# PCB-GPI-JACK.net
KiCad netlist of a schematic drawn in EAGLE
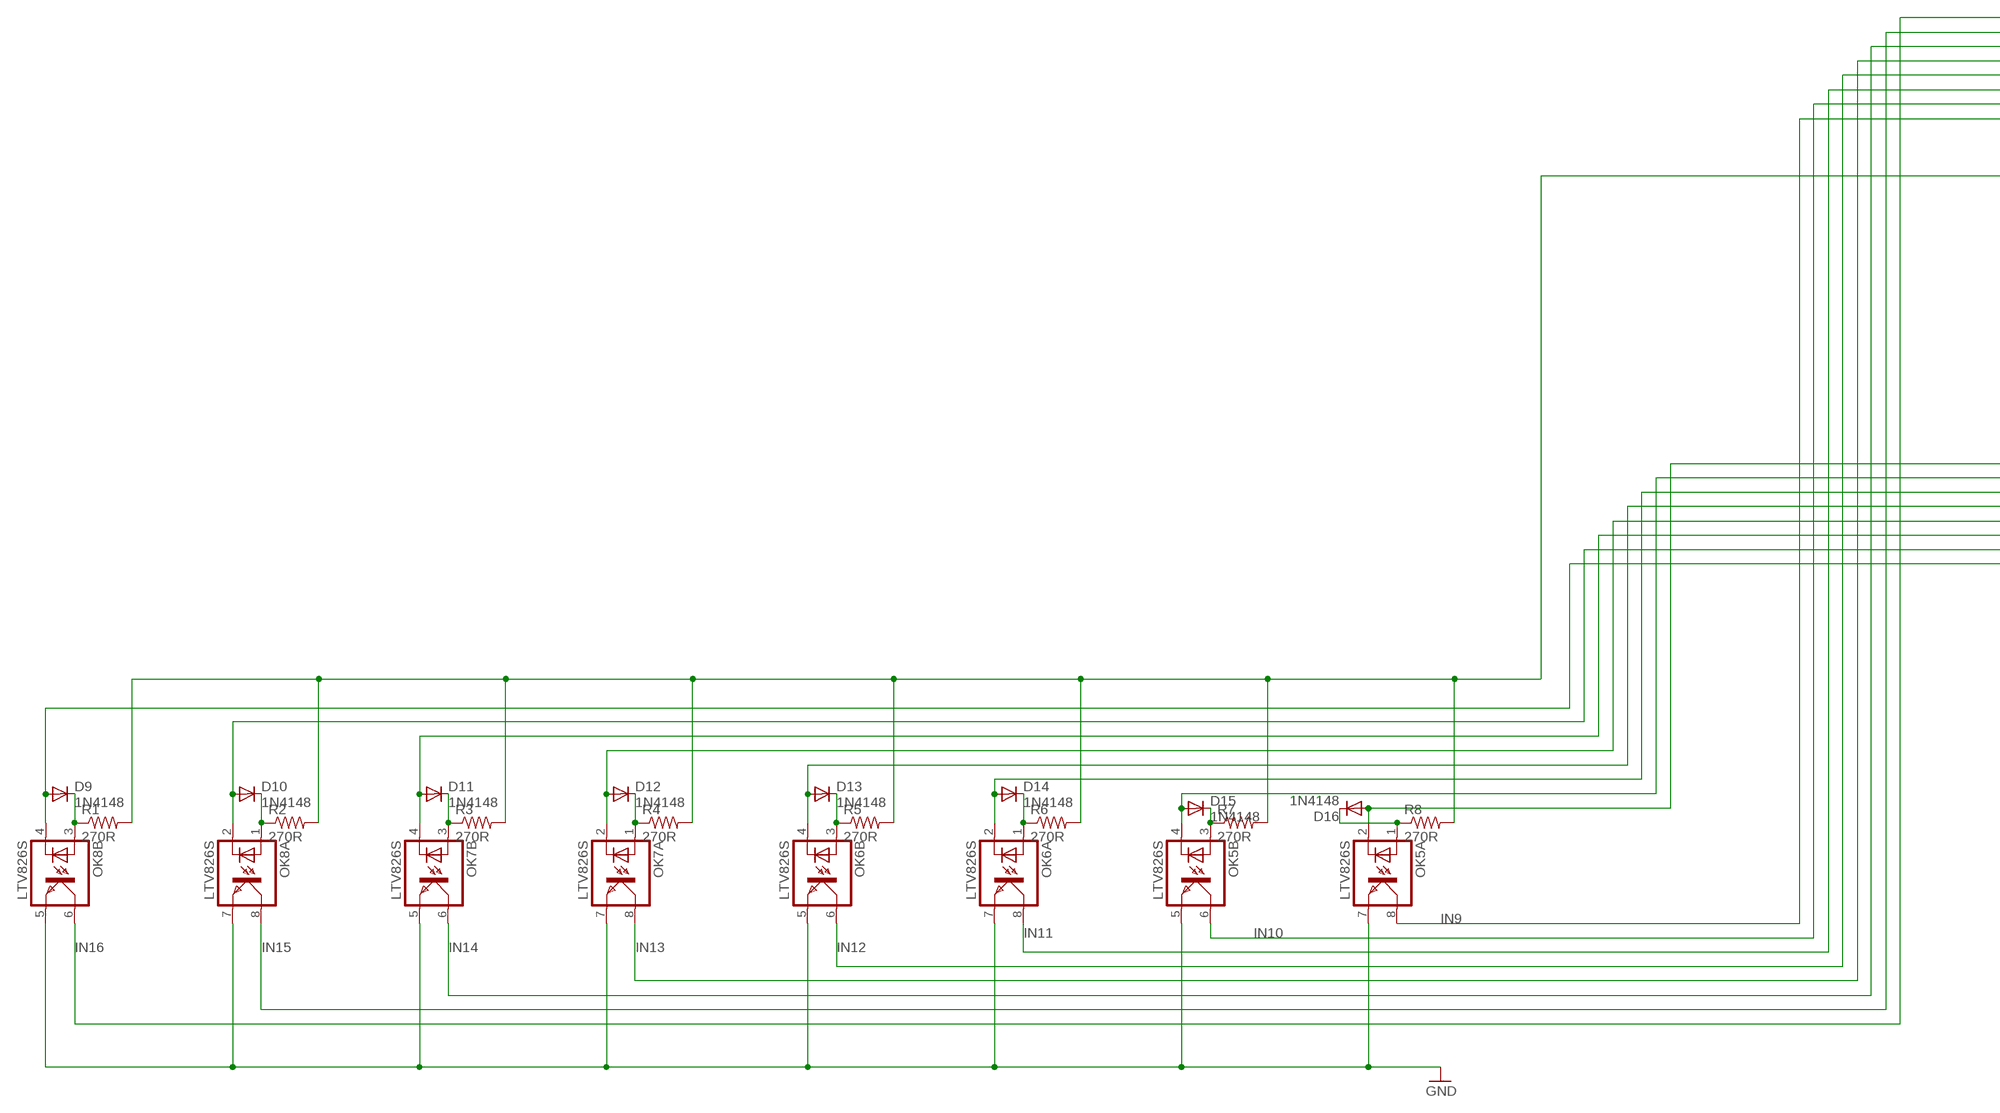
[diagram p0: schematic, sheet 1, part 1 of 2]
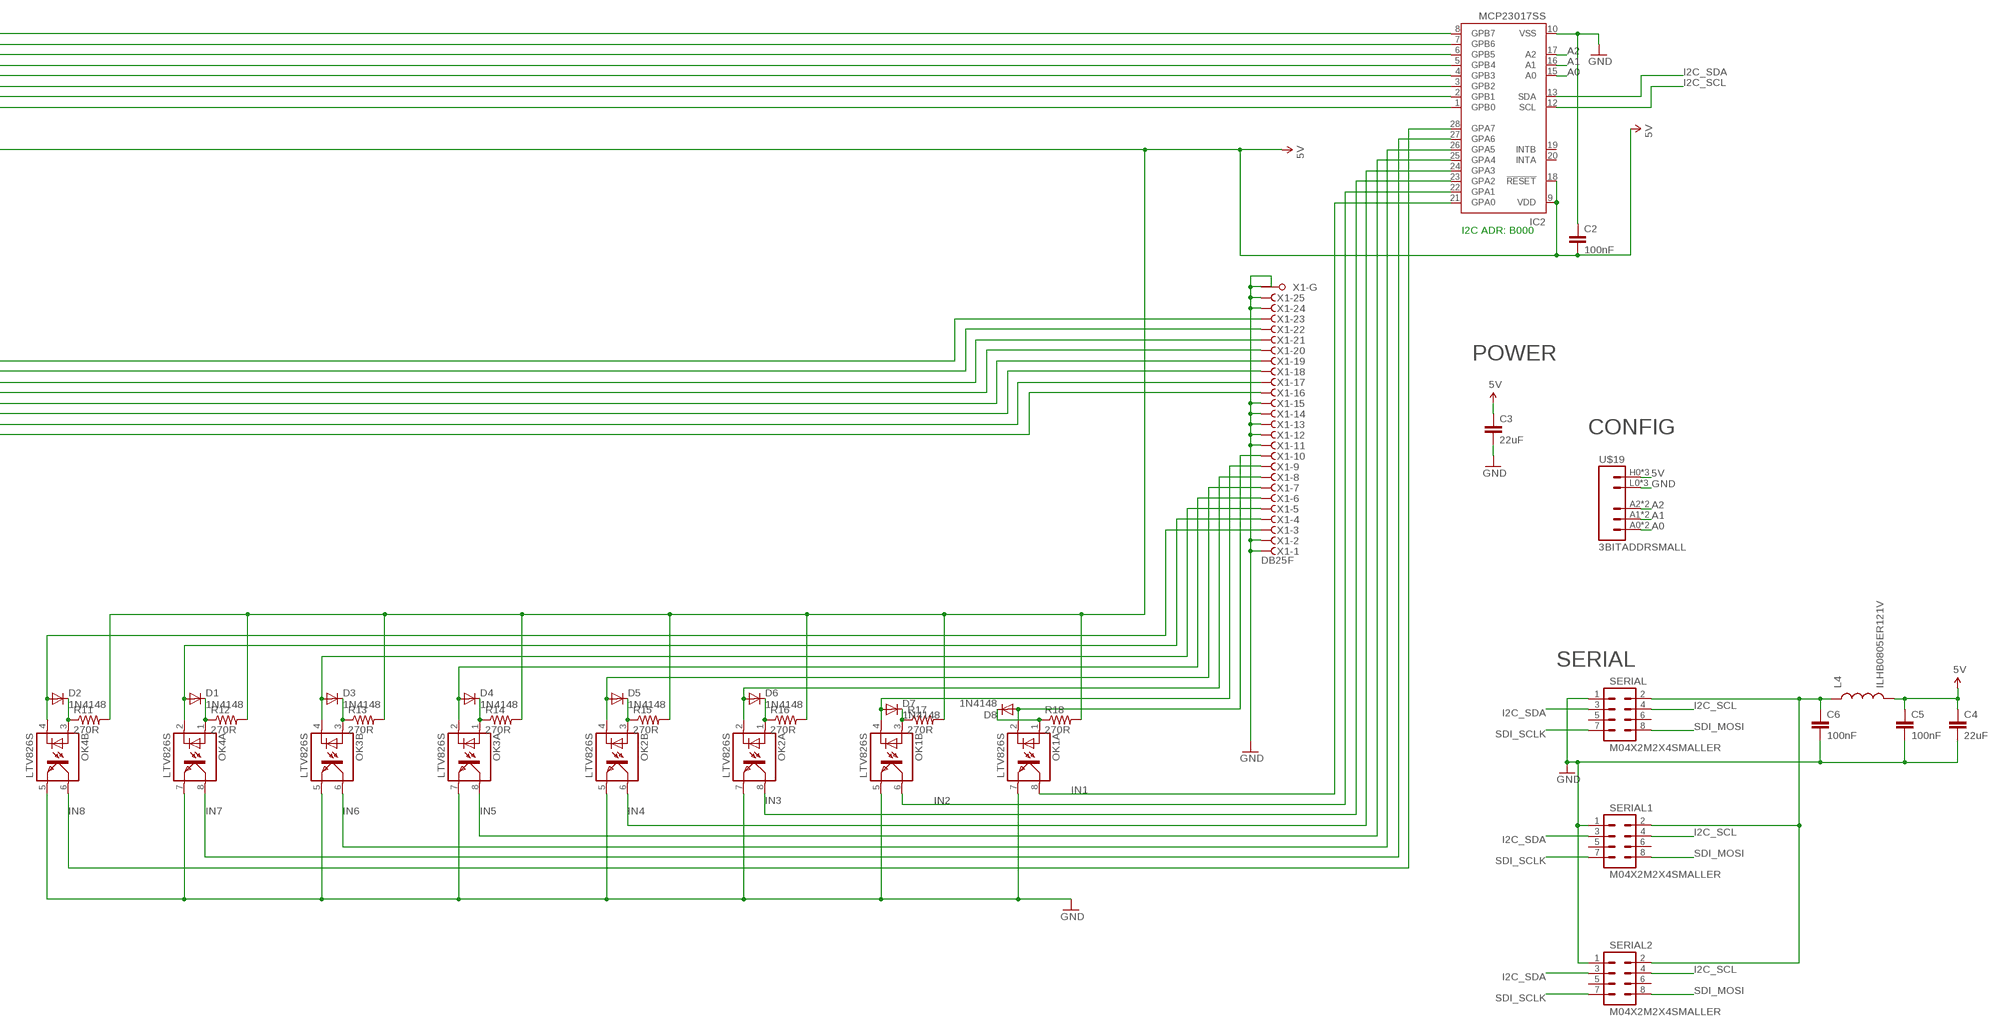
[diagram p1: schematic, sheet 1, part 2 of 2]

(export (version "E")
  (design (tool "Eeschema 10.0.6"))
  (components
    (comp (ref "C2")
      (value "100nF")
      (footprint "eagle-import:0603-CAP")
      (libsource (lib "eagle-import") (part "CAP0603-CAP"))
    )
    (comp (ref "C3")
      (value "22uF")
      (footprint "eagle-import:0805")
      (libsource (lib "eagle-import") (part "CAP0805"))
    )
    (comp (ref "C4")
      (value "22uF")
      (footprint "eagle-import:0805")
      (libsource (lib "eagle-import") (part "CAP0805"))
    )
    (comp (ref "C5")
      (value "100nF")
      (footprint "eagle-import:0603-CAP")
      (libsource (lib "eagle-import") (part "CAP0603-CAP"))
    )
    (comp (ref "C6")
      (value "100nF")
      (footprint "eagle-import:0603-CAP")
      (libsource (lib "eagle-import") (part "CAP0603-CAP"))
    )
    (comp (ref "D1")
      (value "1N4148")
      (footprint "eagle-import:SOD-323")
      (libsource (lib "eagle-import") (part "DIODESOD"))
    )
    (comp (ref "D2")
      (value "1N4148")
      (footprint "eagle-import:SOD-323")
      (libsource (lib "eagle-import") (part "DIODESOD"))
    )
    (comp (ref "D3")
      (value "1N4148")
      (footprint "eagle-import:SOD-323")
      (libsource (lib "eagle-import") (part "DIODESOD"))
    )
    (comp (ref "D4")
      (value "1N4148")
      (footprint "eagle-import:SOD-323")
      (libsource (lib "eagle-import") (part "DIODESOD"))
    )
    (comp (ref "D5")
      (value "1N4148")
      (footprint "eagle-import:SOD-323")
      (libsource (lib "eagle-import") (part "DIODESOD"))
    )
    (comp (ref "D6")
      (value "1N4148")
      (footprint "eagle-import:SOD-323")
      (libsource (lib "eagle-import") (part "DIODESOD"))
    )
    (comp (ref "D7")
      (value "1N4148")
      (footprint "eagle-import:SOD-323")
      (libsource (lib "eagle-import") (part "DIODESOD"))
    )
    (comp (ref "D8")
      (value "1N4148")
      (footprint "eagle-import:SOD-323")
      (libsource (lib "eagle-import") (part "DIODESOD"))
    )
    (comp (ref "D9")
      (value "1N4148")
      (footprint "eagle-import:SOD-323")
      (libsource (lib "eagle-import") (part "DIODESOD"))
    )
    (comp (ref "D10")
      (value "1N4148")
      (footprint "eagle-import:SOD-323")
      (libsource (lib "eagle-import") (part "DIODESOD"))
    )
    (comp (ref "D11")
      (value "1N4148")
      (footprint "eagle-import:SOD-323")
      (libsource (lib "eagle-import") (part "DIODESOD"))
    )
    (comp (ref "D12")
      (value "1N4148")
      (footprint "eagle-import:SOD-323")
      (libsource (lib "eagle-import") (part "DIODESOD"))
    )
    (comp (ref "D13")
      (value "1N4148")
      (footprint "eagle-import:SOD-323")
      (libsource (lib "eagle-import") (part "DIODESOD"))
    )
    (comp (ref "D14")
      (value "1N4148")
      (footprint "eagle-import:SOD-323")
      (libsource (lib "eagle-import") (part "DIODESOD"))
    )
    (comp (ref "D15")
      (value "1N4148")
      (footprint "eagle-import:SOD-323")
      (libsource (lib "eagle-import") (part "DIODESOD"))
    )
    (comp (ref "D16")
      (value "1N4148")
      (footprint "eagle-import:SOD-323")
      (libsource (lib "eagle-import") (part "DIODESOD"))
    )
    (comp (ref "IC2")
      (value "MCP23017SS")
      (footprint "eagle-import:SSOP28")
      (fields (field (name "MF") "MICROCHIP") (field (name "MPN") "MCP23017-E/SS"))
      (libsource (lib "eagle-import") (part "MCP23017SS"))
    )
    (comp (ref "L4")
      (value "ILHB0805ER121V")
      (footprint "eagle-import:0805")
      (libsource (lib "eagle-import") (part "INDUCTOR0805"))
    )
    (comp (ref "OK1")
      (value "LTV826S")
      (footprint "eagle-import:DIL8-SMD")
      (libsource (lib "eagle-import") (part "LTV826S"))
    )
    (comp (ref "OK2")
      (value "LTV826S")
      (footprint "eagle-import:DIL8-SMD")
      (libsource (lib "eagle-import") (part "LTV826S"))
    )
    (comp (ref "OK3")
      (value "LTV826S")
      (footprint "eagle-import:DIL8-SMD")
      (libsource (lib "eagle-import") (part "LTV826S"))
    )
    (comp (ref "OK4")
      (value "LTV826S")
      (footprint "eagle-import:DIL8-SMD")
      (libsource (lib "eagle-import") (part "LTV826S"))
    )
    (comp (ref "OK5")
      (value "LTV826S")
      (footprint "eagle-import:DIL8-SMD")
      (libsource (lib "eagle-import") (part "LTV826S"))
    )
    (comp (ref "OK6")
      (value "LTV826S")
      (footprint "eagle-import:DIL8-SMD")
      (libsource (lib "eagle-import") (part "LTV826S"))
    )
    (comp (ref "OK7")
      (value "LTV826S")
      (footprint "eagle-import:DIL8-SMD")
      (libsource (lib "eagle-import") (part "LTV826S"))
    )
    (comp (ref "OK8")
      (value "LTV826S")
      (footprint "eagle-import:DIL8-SMD")
      (libsource (lib "eagle-import") (part "LTV826S"))
    )
    (comp (ref "R1")
      (value "270R")
      (footprint "eagle-import:0603-RES")
      (libsource (lib "eagle-import") (part "RESISTOR0603-RES"))
    )
    (comp (ref "R2")
      (value "270R")
      (footprint "eagle-import:0603-RES")
      (libsource (lib "eagle-import") (part "RESISTOR0603-RES"))
    )
    (comp (ref "R3")
      (value "270R")
      (footprint "eagle-import:0603-RES")
      (libsource (lib "eagle-import") (part "RESISTOR0603-RES"))
    )
    (comp (ref "R4")
      (value "270R")
      (footprint "eagle-import:0603-RES")
      (libsource (lib "eagle-import") (part "RESISTOR0603-RES"))
    )
    (comp (ref "R5")
      (value "270R")
      (footprint "eagle-import:0603-RES")
      (libsource (lib "eagle-import") (part "RESISTOR0603-RES"))
    )
    (comp (ref "R6")
      (value "270R")
      (footprint "eagle-import:0603-RES")
      (libsource (lib "eagle-import") (part "RESISTOR0603-RES"))
    )
    (comp (ref "R7")
      (value "270R")
      (footprint "eagle-import:0603-RES")
      (libsource (lib "eagle-import") (part "RESISTOR0603-RES"))
    )
    (comp (ref "R8")
      (value "270R")
      (footprint "eagle-import:0603-RES")
      (libsource (lib "eagle-import") (part "RESISTOR0603-RES"))
    )
    (comp (ref "R11")
      (value "270R")
      (footprint "eagle-import:0603-RES")
      (libsource (lib "eagle-import") (part "RESISTOR0603-RES"))
    )
    (comp (ref "R12")
      (value "270R")
      (footprint "eagle-import:0603-RES")
      (libsource (lib "eagle-import") (part "RESISTOR0603-RES"))
    )
    (comp (ref "R13")
      (value "270R")
      (footprint "eagle-import:0603-RES")
      (libsource (lib "eagle-import") (part "RESISTOR0603-RES"))
    )
    (comp (ref "R14")
      (value "270R")
      (footprint "eagle-import:0603-RES")
      (libsource (lib "eagle-import") (part "RESISTOR0603-RES"))
    )
    (comp (ref "R15")
      (value "270R")
      (footprint "eagle-import:0603-RES")
      (libsource (lib "eagle-import") (part "RESISTOR0603-RES"))
    )
    (comp (ref "R16")
      (value "270R")
      (footprint "eagle-import:0603-RES")
      (libsource (lib "eagle-import") (part "RESISTOR0603-RES"))
    )
    (comp (ref "R17")
      (value "270R")
      (footprint "eagle-import:0603-RES")
      (libsource (lib "eagle-import") (part "RESISTOR0603-RES"))
    )
    (comp (ref "R18")
      (value "270R")
      (footprint "eagle-import:0603-RES")
      (libsource (lib "eagle-import") (part "RESISTOR0603-RES"))
    )
    (comp (ref "SERIAL")
      (value "M04X2M2X4SMALLER")
      (footprint "eagle-import:M2X4SMALLER")
      (libsource (lib "eagle-import") (part "M04X2M2X4SMALLER"))
    )
    (comp (ref "SERIAL1")
      (value "M04X2M2X4SMALLER")
      (footprint "eagle-import:M2X4SMALLER")
      (libsource (lib "eagle-import") (part "M04X2M2X4SMALLER"))
    )
    (comp (ref "SERIAL2")
      (value "M04X2M2X4SMALLER")
      (footprint "eagle-import:M2X4SMALLER")
      (libsource (lib "eagle-import") (part "M04X2M2X4SMALLER"))
    )
    (comp (ref "U$19")
      (value "3BITADDRSMALL")
      (footprint "eagle-import:3BITADDR_SMALL")
      (libsource (lib "eagle-import") (part "3BITADDRSMALL"))
    )
    (comp (ref "X1")
      (value "DB25F")
      (footprint "eagle-import:F25HP")
      (libsource (lib "eagle-import") (part "F25HPS"))
    )
  )
  (nets
    (net (code "1") (name "5V") (class "Default")
      (node (ref "C2") (pin "2") (pinfunction "2_2") (pintype "passive"))
      (node (ref "C3") (pin "1") (pinfunction "1_1") (pintype "passive"))
      (node (ref "C4") (pin "1") (pinfunction "1_1") (pintype "passive"))
      (node (ref "C5") (pin "1") (pinfunction "1_1") (pintype "passive"))
      (node (ref "IC2") (pin "18") (pinfunction "~{RESET}_18") (pintype "input"))
      (node (ref "IC2") (pin "9") (pinfunction "VDD_9") (pintype "power_in"))
      (node (ref "L4") (pin "2") (pinfunction "2_2") (pintype "passive"))
      (node (ref "R1") (pin "2") (pinfunction "2_2") (pintype "passive"))
      (node (ref "R11") (pin "2") (pinfunction "2_2") (pintype "passive"))
      (node (ref "R12") (pin "2") (pinfunction "2_2") (pintype "passive"))
      (node (ref "R13") (pin "2") (pinfunction "2_2") (pintype "passive"))
      (node (ref "R14") (pin "2") (pinfunction "2_2") (pintype "passive"))
      (node (ref "R15") (pin "2") (pinfunction "2_2") (pintype "passive"))
      (node (ref "R16") (pin "2") (pinfunction "2_2") (pintype "passive"))
      (node (ref "R17") (pin "2") (pinfunction "2_2") (pintype "passive"))
      (node (ref "R18") (pin "2") (pinfunction "2_2") (pintype "passive"))
      (node (ref "R2") (pin "2") (pinfunction "2_2") (pintype "passive"))
      (node (ref "R3") (pin "2") (pinfunction "2_2") (pintype "passive"))
      (node (ref "R4") (pin "2") (pinfunction "2_2") (pintype "passive"))
      (node (ref "R5") (pin "2") (pinfunction "2_2") (pintype "passive"))
      (node (ref "R6") (pin "2") (pinfunction "2_2") (pintype "passive"))
      (node (ref "R7") (pin "2") (pinfunction "2_2") (pintype "passive"))
      (node (ref "R8") (pin "2") (pinfunction "2_2") (pintype "passive"))
      (node (ref "U$19") (pin "H0") (pinfunction "VCC_H0") (pintype "passive"))
      (node (ref "U$19") (pin "H1") (pinfunction "VCC_H1") (pintype "passive"))
      (node (ref "U$19") (pin "H2") (pinfunction "VCC_H2") (pintype "passive"))
    )
    (net (code "2") (name "A0") (class "Default")
      (node (ref "IC2") (pin "15") (pinfunction "A0_15") (pintype "input"))
      (node (ref "U$19") (pin "A0") (pinfunction "A0_A0") (pintype "passive"))
      (node (ref "U$19") (pin "AS0") (pinfunction "A0_AS0") (pintype "passive"))
    )
    (net (code "3") (name "A1") (class "Default")
      (node (ref "IC2") (pin "16") (pinfunction "A1_16") (pintype "input"))
      (node (ref "U$19") (pin "A1") (pinfunction "A1_A1") (pintype "passive"))
      (node (ref "U$19") (pin "AS1") (pinfunction "A1_AS1") (pintype "passive"))
    )
    (net (code "4") (name "A2") (class "Default")
      (node (ref "IC2") (pin "17") (pinfunction "A2_17") (pintype "input"))
      (node (ref "U$19") (pin "A2") (pinfunction "A2_A2") (pintype "passive"))
      (node (ref "U$19") (pin "AS2") (pinfunction "A2_AS2") (pintype "passive"))
    )
    (net (code "5") (name "GND") (class "Default")
      (node (ref "C2") (pin "1") (pinfunction "1_1") (pintype "passive"))
      (node (ref "C3") (pin "2") (pinfunction "2_2") (pintype "passive"))
      (node (ref "C4") (pin "2") (pinfunction "2_2") (pintype "passive"))
      (node (ref "C5") (pin "2") (pinfunction "2_2") (pintype "passive"))
      (node (ref "C6") (pin "2") (pinfunction "2_2") (pintype "passive"))
      (node (ref "IC2") (pin "10") (pinfunction "VSS_10") (pintype "power_in"))
      (node (ref "OK1") (pin "5") (pinfunction "EMIT_5") (pintype "passive"))
      (node (ref "OK1") (pin "7") (pinfunction "EMIT_7") (pintype "passive"))
      (node (ref "OK2") (pin "5") (pinfunction "EMIT_5") (pintype "passive"))
      (node (ref "OK2") (pin "7") (pinfunction "EMIT_7") (pintype "passive"))
      (node (ref "OK3") (pin "5") (pinfunction "EMIT_5") (pintype "passive"))
      (node (ref "OK3") (pin "7") (pinfunction "EMIT_7") (pintype "passive"))
      (node (ref "OK4") (pin "5") (pinfunction "EMIT_5") (pintype "passive"))
      (node (ref "OK4") (pin "7") (pinfunction "EMIT_7") (pintype "passive"))
      (node (ref "OK5") (pin "5") (pinfunction "EMIT_5") (pintype "passive"))
      (node (ref "OK5") (pin "7") (pinfunction "EMIT_7") (pintype "passive"))
      (node (ref "OK6") (pin "5") (pinfunction "EMIT_5") (pintype "passive"))
      (node (ref "OK6") (pin "7") (pinfunction "EMIT_7") (pintype "passive"))
      (node (ref "OK7") (pin "5") (pinfunction "EMIT_5") (pintype "passive"))
      (node (ref "OK7") (pin "7") (pinfunction "EMIT_7") (pintype "passive"))
      (node (ref "OK8") (pin "5") (pinfunction "EMIT_5") (pintype "passive"))
      (node (ref "OK8") (pin "7") (pinfunction "EMIT_7") (pintype "passive"))
      (node (ref "SERIAL") (pin "1") (pinfunction "1_1") (pintype "passive"))
      (node (ref "SERIAL1") (pin "1") (pinfunction "1_1") (pintype "passive"))
      (node (ref "SERIAL2") (pin "1") (pinfunction "1_1") (pintype "passive"))
      (node (ref "U$19") (pin "L0") (pinfunction "GND_L0") (pintype "passive"))
      (node (ref "U$19") (pin "L1") (pinfunction "GND_L1") (pintype "passive"))
      (node (ref "U$19") (pin "L2") (pinfunction "GND_L2") (pintype "passive"))
      (node (ref "X1") (pin "1") (pinfunction "F_1") (pintype "passive"))
      (node (ref "X1") (pin "11") (pinfunction "F_11") (pintype "passive"))
      (node (ref "X1") (pin "12") (pinfunction "F_12") (pintype "passive"))
      (node (ref "X1") (pin "13") (pinfunction "F_13") (pintype "passive"))
      (node (ref "X1") (pin "14") (pinfunction "F_14") (pintype "passive"))
      (node (ref "X1") (pin "15") (pinfunction "F_15") (pintype "passive"))
      (node (ref "X1") (pin "2") (pinfunction "F_2") (pintype "passive"))
      (node (ref "X1") (pin "24") (pinfunction "F_24") (pintype "passive"))
      (node (ref "X1") (pin "25") (pinfunction "F_25") (pintype "passive"))
      (node (ref "X1") (pin "G1") (pinfunction "G1_G1") (pintype "passive"))
      (node (ref "X1") (pin "G2") (pinfunction "G2_G2") (pintype "passive"))
    )
    (net (code "6") (name "I2C_SCL") (class "Default")
      (node (ref "IC2") (pin "12") (pinfunction "SCL_12") (pintype "input"))
      (node (ref "SERIAL") (pin "4") (pinfunction "4_4") (pintype "passive"))
      (node (ref "SERIAL1") (pin "4") (pinfunction "4_4") (pintype "passive"))
      (node (ref "SERIAL2") (pin "4") (pinfunction "4_4") (pintype "passive"))
    )
    (net (code "7") (name "I2C_SDA") (class "Default")
      (node (ref "IC2") (pin "13") (pinfunction "SDA_13") (pintype "bidirectional"))
      (node (ref "SERIAL") (pin "3") (pinfunction "3_3") (pintype "passive"))
      (node (ref "SERIAL1") (pin "3") (pinfunction "3_3") (pintype "passive"))
      (node (ref "SERIAL2") (pin "3") (pinfunction "3_3") (pintype "passive"))
    )
    (net (code "8") (name "IN1") (class "Default")
      (node (ref "IC2") (pin "21") (pinfunction "GPA0_21") (pintype "bidirectional"))
      (node (ref "OK1") (pin "8") (pinfunction "COL_8") (pintype "passive"))
    )
    (net (code "9") (name "IN2") (class "Default")
      (node (ref "IC2") (pin "22") (pinfunction "GPA1_22") (pintype "bidirectional"))
      (node (ref "OK1") (pin "6") (pinfunction "COL_6") (pintype "passive"))
    )
    (net (code "10") (name "IN3") (class "Default")
      (node (ref "IC2") (pin "23") (pinfunction "GPA2_23") (pintype "bidirectional"))
      (node (ref "OK2") (pin "8") (pinfunction "COL_8") (pintype "passive"))
    )
    (net (code "11") (name "IN4") (class "Default")
      (node (ref "IC2") (pin "24") (pinfunction "GPA3_24") (pintype "bidirectional"))
      (node (ref "OK2") (pin "6") (pinfunction "COL_6") (pintype "passive"))
    )
    (net (code "12") (name "IN5") (class "Default")
      (node (ref "IC2") (pin "25") (pinfunction "GPA4_25") (pintype "bidirectional"))
      (node (ref "OK3") (pin "8") (pinfunction "COL_8") (pintype "passive"))
    )
    (net (code "13") (name "IN6") (class "Default")
      (node (ref "IC2") (pin "26") (pinfunction "GPA5_26") (pintype "bidirectional"))
      (node (ref "OK3") (pin "6") (pinfunction "COL_6") (pintype "passive"))
    )
    (net (code "14") (name "IN7") (class "Default")
      (node (ref "IC2") (pin "27") (pinfunction "GPA6_27") (pintype "bidirectional"))
      (node (ref "OK4") (pin "8") (pinfunction "COL_8") (pintype "passive"))
    )
    (net (code "15") (name "IN8") (class "Default")
      (node (ref "IC2") (pin "28") (pinfunction "GPA7_28") (pintype "bidirectional"))
      (node (ref "OK4") (pin "6") (pinfunction "COL_6") (pintype "passive"))
    )
    (net (code "16") (name "IN9") (class "Default")
      (node (ref "IC2") (pin "1") (pinfunction "GPB0_1") (pintype "bidirectional"))
      (node (ref "OK5") (pin "8") (pinfunction "COL_8") (pintype "passive"))
    )
    (net (code "17") (name "IN10") (class "Default")
      (node (ref "IC2") (pin "2") (pinfunction "GPB1_2") (pintype "bidirectional"))
      (node (ref "OK5") (pin "6") (pinfunction "COL_6") (pintype "passive"))
    )
    (net (code "18") (name "IN11") (class "Default")
      (node (ref "IC2") (pin "3") (pinfunction "GPB2_3") (pintype "bidirectional"))
      (node (ref "OK6") (pin "8") (pinfunction "COL_8") (pintype "passive"))
    )
    (net (code "19") (name "IN12") (class "Default")
      (node (ref "IC2") (pin "4") (pinfunction "GPB3_4") (pintype "bidirectional"))
      (node (ref "OK6") (pin "6") (pinfunction "COL_6") (pintype "passive"))
    )
    (net (code "20") (name "IN13") (class "Default")
      (node (ref "IC2") (pin "5") (pinfunction "GPB4_5") (pintype "bidirectional"))
      (node (ref "OK7") (pin "8") (pinfunction "COL_8") (pintype "passive"))
    )
    (net (code "21") (name "IN14") (class "Default")
      (node (ref "IC2") (pin "6") (pinfunction "GPB5_6") (pintype "bidirectional"))
      (node (ref "OK7") (pin "6") (pinfunction "COL_6") (pintype "passive"))
    )
    (net (code "22") (name "IN15") (class "Default")
      (node (ref "IC2") (pin "7") (pinfunction "GPB6_7") (pintype "bidirectional"))
      (node (ref "OK8") (pin "8") (pinfunction "COL_8") (pintype "passive"))
    )
    (net (code "23") (name "IN16") (class "Default")
      (node (ref "IC2") (pin "8") (pinfunction "GPB7_8") (pintype "bidirectional"))
      (node (ref "OK8") (pin "6") (pinfunction "COL_6") (pintype "passive"))
    )
    (net (code "24") (name "Net-(C6-Pad1)") (class "Default")
      (node (ref "C6") (pin "1") (pinfunction "1_1") (pintype "passive"))
      (node (ref "L4") (pin "1") (pinfunction "1_1") (pintype "passive"))
      (node (ref "SERIAL") (pin "2") (pinfunction "2_2") (pintype "passive"))
      (node (ref "SERIAL1") (pin "2") (pinfunction "2_2") (pintype "passive"))
      (node (ref "SERIAL2") (pin "2") (pinfunction "2_2") (pintype "passive"))
    )
    (net (code "25") (name "Net-(D1-A)") (class "Default")
      (node (ref "D1") (pin "2") (pinfunction "A_2") (pintype "passive"))
      (node (ref "OK4") (pin "2") (pinfunction "C_2") (pintype "passive"))
      (node (ref "X1") (pin "4") (pinfunction "F_4") (pintype "passive"))
    )
    (net (code "26") (name "Net-(D1-C)") (class "Default")
      (node (ref "D1") (pin "1") (pinfunction "C_1") (pintype "passive"))
      (node (ref "OK4") (pin "1") (pinfunction "A_1") (pintype "passive"))
      (node (ref "R12") (pin "1") (pinfunction "1_1") (pintype "passive"))
    )
    (net (code "27") (name "Net-(D2-A)") (class "Default")
      (node (ref "D2") (pin "2") (pinfunction "A_2") (pintype "passive"))
      (node (ref "OK4") (pin "4") (pinfunction "C_4") (pintype "passive"))
      (node (ref "X1") (pin "3") (pinfunction "F_3") (pintype "passive"))
    )
    (net (code "28") (name "Net-(D2-C)") (class "Default")
      (node (ref "D2") (pin "1") (pinfunction "C_1") (pintype "passive"))
      (node (ref "OK4") (pin "3") (pinfunction "A_3") (pintype "passive"))
      (node (ref "R11") (pin "1") (pinfunction "1_1") (pintype "passive"))
    )
    (net (code "29") (name "Net-(D3-A)") (class "Default")
      (node (ref "D3") (pin "2") (pinfunction "A_2") (pintype "passive"))
      (node (ref "OK3") (pin "4") (pinfunction "C_4") (pintype "passive"))
      (node (ref "X1") (pin "5") (pinfunction "F_5") (pintype "passive"))
    )
    (net (code "30") (name "Net-(D3-C)") (class "Default")
      (node (ref "D3") (pin "1") (pinfunction "C_1") (pintype "passive"))
      (node (ref "OK3") (pin "3") (pinfunction "A_3") (pintype "passive"))
      (node (ref "R13") (pin "1") (pinfunction "1_1") (pintype "passive"))
    )
    (net (code "31") (name "Net-(D4-A)") (class "Default")
      (node (ref "D4") (pin "2") (pinfunction "A_2") (pintype "passive"))
      (node (ref "OK3") (pin "2") (pinfunction "C_2") (pintype "passive"))
      (node (ref "X1") (pin "6") (pinfunction "F_6") (pintype "passive"))
    )
    (net (code "32") (name "Net-(D4-C)") (class "Default")
      (node (ref "D4") (pin "1") (pinfunction "C_1") (pintype "passive"))
      (node (ref "OK3") (pin "1") (pinfunction "A_1") (pintype "passive"))
      (node (ref "R14") (pin "1") (pinfunction "1_1") (pintype "passive"))
    )
    (net (code "33") (name "Net-(D5-A)") (class "Default")
      (node (ref "D5") (pin "2") (pinfunction "A_2") (pintype "passive"))
      (node (ref "OK2") (pin "4") (pinfunction "C_4") (pintype "passive"))
      (node (ref "X1") (pin "7") (pinfunction "F_7") (pintype "passive"))
    )
    (net (code "34") (name "Net-(D5-C)") (class "Default")
      (node (ref "D5") (pin "1") (pinfunction "C_1") (pintype "passive"))
      (node (ref "OK2") (pin "3") (pinfunction "A_3") (pintype "passive"))
      (node (ref "R15") (pin "1") (pinfunction "1_1") (pintype "passive"))
    )
    (net (code "35") (name "Net-(D6-A)") (class "Default")
      (node (ref "D6") (pin "2") (pinfunction "A_2") (pintype "passive"))
      (node (ref "OK2") (pin "2") (pinfunction "C_2") (pintype "passive"))
      (node (ref "X1") (pin "8") (pinfunction "F_8") (pintype "passive"))
    )
    (net (code "36") (name "Net-(D6-C)") (class "Default")
      (node (ref "D6") (pin "1") (pinfunction "C_1") (pintype "passive"))
      (node (ref "OK2") (pin "1") (pinfunction "A_1") (pintype "passive"))
      (node (ref "R16") (pin "1") (pinfunction "1_1") (pintype "passive"))
    )
    (net (code "37") (name "Net-(D7-A)") (class "Default")
      (node (ref "D7") (pin "2") (pinfunction "A_2") (pintype "passive"))
      (node (ref "OK1") (pin "4") (pinfunction "C_4") (pintype "passive"))
      (node (ref "X1") (pin "9") (pinfunction "F_9") (pintype "passive"))
    )
    (net (code "38") (name "Net-(D7-C)") (class "Default")
      (node (ref "D7") (pin "1") (pinfunction "C_1") (pintype "passive"))
      (node (ref "OK1") (pin "3") (pinfunction "A_3") (pintype "passive"))
      (node (ref "R17") (pin "1") (pinfunction "1_1") (pintype "passive"))
    )
    (net (code "39") (name "Net-(D8-A)") (class "Default")
      (node (ref "D8") (pin "2") (pinfunction "A_2") (pintype "passive"))
      (node (ref "OK1") (pin "2") (pinfunction "C_2") (pintype "passive"))
      (node (ref "X1") (pin "10") (pinfunction "F_10") (pintype "passive"))
    )
    (net (code "40") (name "Net-(D8-C)") (class "Default")
      (node (ref "D8") (pin "1") (pinfunction "C_1") (pintype "passive"))
      (node (ref "OK1") (pin "1") (pinfunction "A_1") (pintype "passive"))
      (node (ref "R18") (pin "1") (pinfunction "1_1") (pintype "passive"))
    )
    (net (code "41") (name "Net-(D9-A)") (class "Default")
      (node (ref "D9") (pin "2") (pinfunction "A_2") (pintype "passive"))
      (node (ref "OK8") (pin "4") (pinfunction "C_4") (pintype "passive"))
      (node (ref "X1") (pin "16") (pinfunction "F_16") (pintype "passive"))
    )
    (net (code "42") (name "Net-(D9-C)") (class "Default")
      (node (ref "D9") (pin "1") (pinfunction "C_1") (pintype "passive"))
      (node (ref "OK8") (pin "3") (pinfunction "A_3") (pintype "passive"))
      (node (ref "R1") (pin "1") (pinfunction "1_1") (pintype "passive"))
    )
    (net (code "43") (name "Net-(D10-A)") (class "Default")
      (node (ref "D10") (pin "2") (pinfunction "A_2") (pintype "passive"))
      (node (ref "OK8") (pin "2") (pinfunction "C_2") (pintype "passive"))
      (node (ref "X1") (pin "17") (pinfunction "F_17") (pintype "passive"))
    )
    (net (code "44") (name "Net-(D10-C)") (class "Default")
      (node (ref "D10") (pin "1") (pinfunction "C_1") (pintype "passive"))
      (node (ref "OK8") (pin "1") (pinfunction "A_1") (pintype "passive"))
      (node (ref "R2") (pin "1") (pinfunction "1_1") (pintype "passive"))
    )
    (net (code "45") (name "Net-(D11-A)") (class "Default")
      (node (ref "D11") (pin "2") (pinfunction "A_2") (pintype "passive"))
      (node (ref "OK7") (pin "4") (pinfunction "C_4") (pintype "passive"))
      (node (ref "X1") (pin "18") (pinfunction "F_18") (pintype "passive"))
    )
    (net (code "46") (name "Net-(D11-C)") (class "Default")
      (node (ref "D11") (pin "1") (pinfunction "C_1") (pintype "passive"))
      (node (ref "OK7") (pin "3") (pinfunction "A_3") (pintype "passive"))
      (node (ref "R3") (pin "1") (pinfunction "1_1") (pintype "passive"))
    )
    (net (code "47") (name "Net-(D12-A)") (class "Default")
      (node (ref "D12") (pin "2") (pinfunction "A_2") (pintype "passive"))
      (node (ref "OK7") (pin "2") (pinfunction "C_2") (pintype "passive"))
      (node (ref "X1") (pin "19") (pinfunction "F_19") (pintype "passive"))
    )
    (net (code "48") (name "Net-(D12-C)") (class "Default")
      (node (ref "D12") (pin "1") (pinfunction "C_1") (pintype "passive"))
      (node (ref "OK7") (pin "1") (pinfunction "A_1") (pintype "passive"))
      (node (ref "R4") (pin "1") (pinfunction "1_1") (pintype "passive"))
    )
    (net (code "49") (name "Net-(D13-A)") (class "Default")
      (node (ref "D13") (pin "2") (pinfunction "A_2") (pintype "passive"))
      (node (ref "OK6") (pin "4") (pinfunction "C_4") (pintype "passive"))
      (node (ref "X1") (pin "20") (pinfunction "F_20") (pintype "passive"))
    )
    (net (code "50") (name "Net-(D13-C)") (class "Default")
      (node (ref "D13") (pin "1") (pinfunction "C_1") (pintype "passive"))
      (node (ref "OK6") (pin "3") (pinfunction "A_3") (pintype "passive"))
      (node (ref "R5") (pin "1") (pinfunction "1_1") (pintype "passive"))
    )
    (net (code "51") (name "Net-(D14-A)") (class "Default")
      (node (ref "D14") (pin "2") (pinfunction "A_2") (pintype "passive"))
      (node (ref "OK6") (pin "2") (pinfunction "C_2") (pintype "passive"))
      (node (ref "X1") (pin "21") (pinfunction "F_21") (pintype "passive"))
    )
    (net (code "52") (name "Net-(D14-C)") (class "Default")
      (node (ref "D14") (pin "1") (pinfunction "C_1") (pintype "passive"))
      (node (ref "OK6") (pin "1") (pinfunction "A_1") (pintype "passive"))
      (node (ref "R6") (pin "1") (pinfunction "1_1") (pintype "passive"))
    )
    (net (code "53") (name "Net-(D15-A)") (class "Default")
      (node (ref "D15") (pin "2") (pinfunction "A_2") (pintype "passive"))
      (node (ref "OK5") (pin "4") (pinfunction "C_4") (pintype "passive"))
      (node (ref "X1") (pin "22") (pinfunction "F_22") (pintype "passive"))
    )
    (net (code "54") (name "Net-(D15-C)") (class "Default")
      (node (ref "D15") (pin "1") (pinfunction "C_1") (pintype "passive"))
      (node (ref "OK5") (pin "3") (pinfunction "A_3") (pintype "passive"))
      (node (ref "R7") (pin "1") (pinfunction "1_1") (pintype "passive"))
    )
    (net (code "55") (name "Net-(D16-A)") (class "Default")
      (node (ref "D16") (pin "2") (pinfunction "A_2") (pintype "passive"))
      (node (ref "OK5") (pin "2") (pinfunction "C_2") (pintype "passive"))
      (node (ref "X1") (pin "23") (pinfunction "F_23") (pintype "passive"))
    )
    (net (code "56") (name "Net-(D16-C)") (class "Default")
      (node (ref "D16") (pin "1") (pinfunction "C_1") (pintype "passive"))
      (node (ref "OK5") (pin "1") (pinfunction "A_1") (pintype "passive"))
      (node (ref "R8") (pin "1") (pinfunction "1_1") (pintype "passive"))
    )
    (net (code "57") (name "SDI_MOSI") (class "Default")
      (node (ref "SERIAL") (pin "8") (pinfunction "8_8") (pintype "passive"))
      (node (ref "SERIAL1") (pin "8") (pinfunction "8_8") (pintype "passive"))
      (node (ref "SERIAL2") (pin "8") (pinfunction "8_8") (pintype "passive"))
    )
    (net (code "58") (name "SDI_SCLK") (class "Default")
      (node (ref "SERIAL") (pin "7") (pinfunction "7_7") (pintype "passive"))
      (node (ref "SERIAL1") (pin "7") (pinfunction "7_7") (pintype "passive"))
      (node (ref "SERIAL2") (pin "7") (pinfunction "7_7") (pintype "passive"))
    )
    (net (code "59") (name "unconnected-(IC2-INTA-Pad20)") (class "Default")
      (node (ref "IC2") (pin "20") (pinfunction "INTA_20") (pintype "output"))
    )
    (net (code "60") (name "unconnected-(IC2-INTB-Pad19)") (class "Default")
      (node (ref "IC2") (pin "19") (pinfunction "INTB_19") (pintype "output"))
    )
    (net (code "61") (name "unconnected-(SERIAL-Pad5)") (class "Default")
      (node (ref "SERIAL") (pin "5") (pinfunction "5_5") (pintype "passive"))
    )
    (net (code "62") (name "unconnected-(SERIAL-Pad6)") (class "Default")
      (node (ref "SERIAL") (pin "6") (pinfunction "6_6") (pintype "passive"))
    )
    (net (code "63") (name "unconnected-(SERIAL1-Pad5)") (class "Default")
      (node (ref "SERIAL1") (pin "5") (pinfunction "5_5") (pintype "passive"))
    )
    (net (code "64") (name "unconnected-(SERIAL1-Pad6)") (class "Default")
      (node (ref "SERIAL1") (pin "6") (pinfunction "6_6") (pintype "passive"))
    )
    (net (code "65") (name "unconnected-(SERIAL2-Pad5)") (class "Default")
      (node (ref "SERIAL2") (pin "5") (pinfunction "5_5") (pintype "passive"))
    )
    (net (code "66") (name "unconnected-(SERIAL2-Pad6)") (class "Default")
      (node (ref "SERIAL2") (pin "6") (pinfunction "6_6") (pintype "passive"))
    )
  )
)
